# untitled.net
KiCad netlist of a schematic drawn in EAGLE
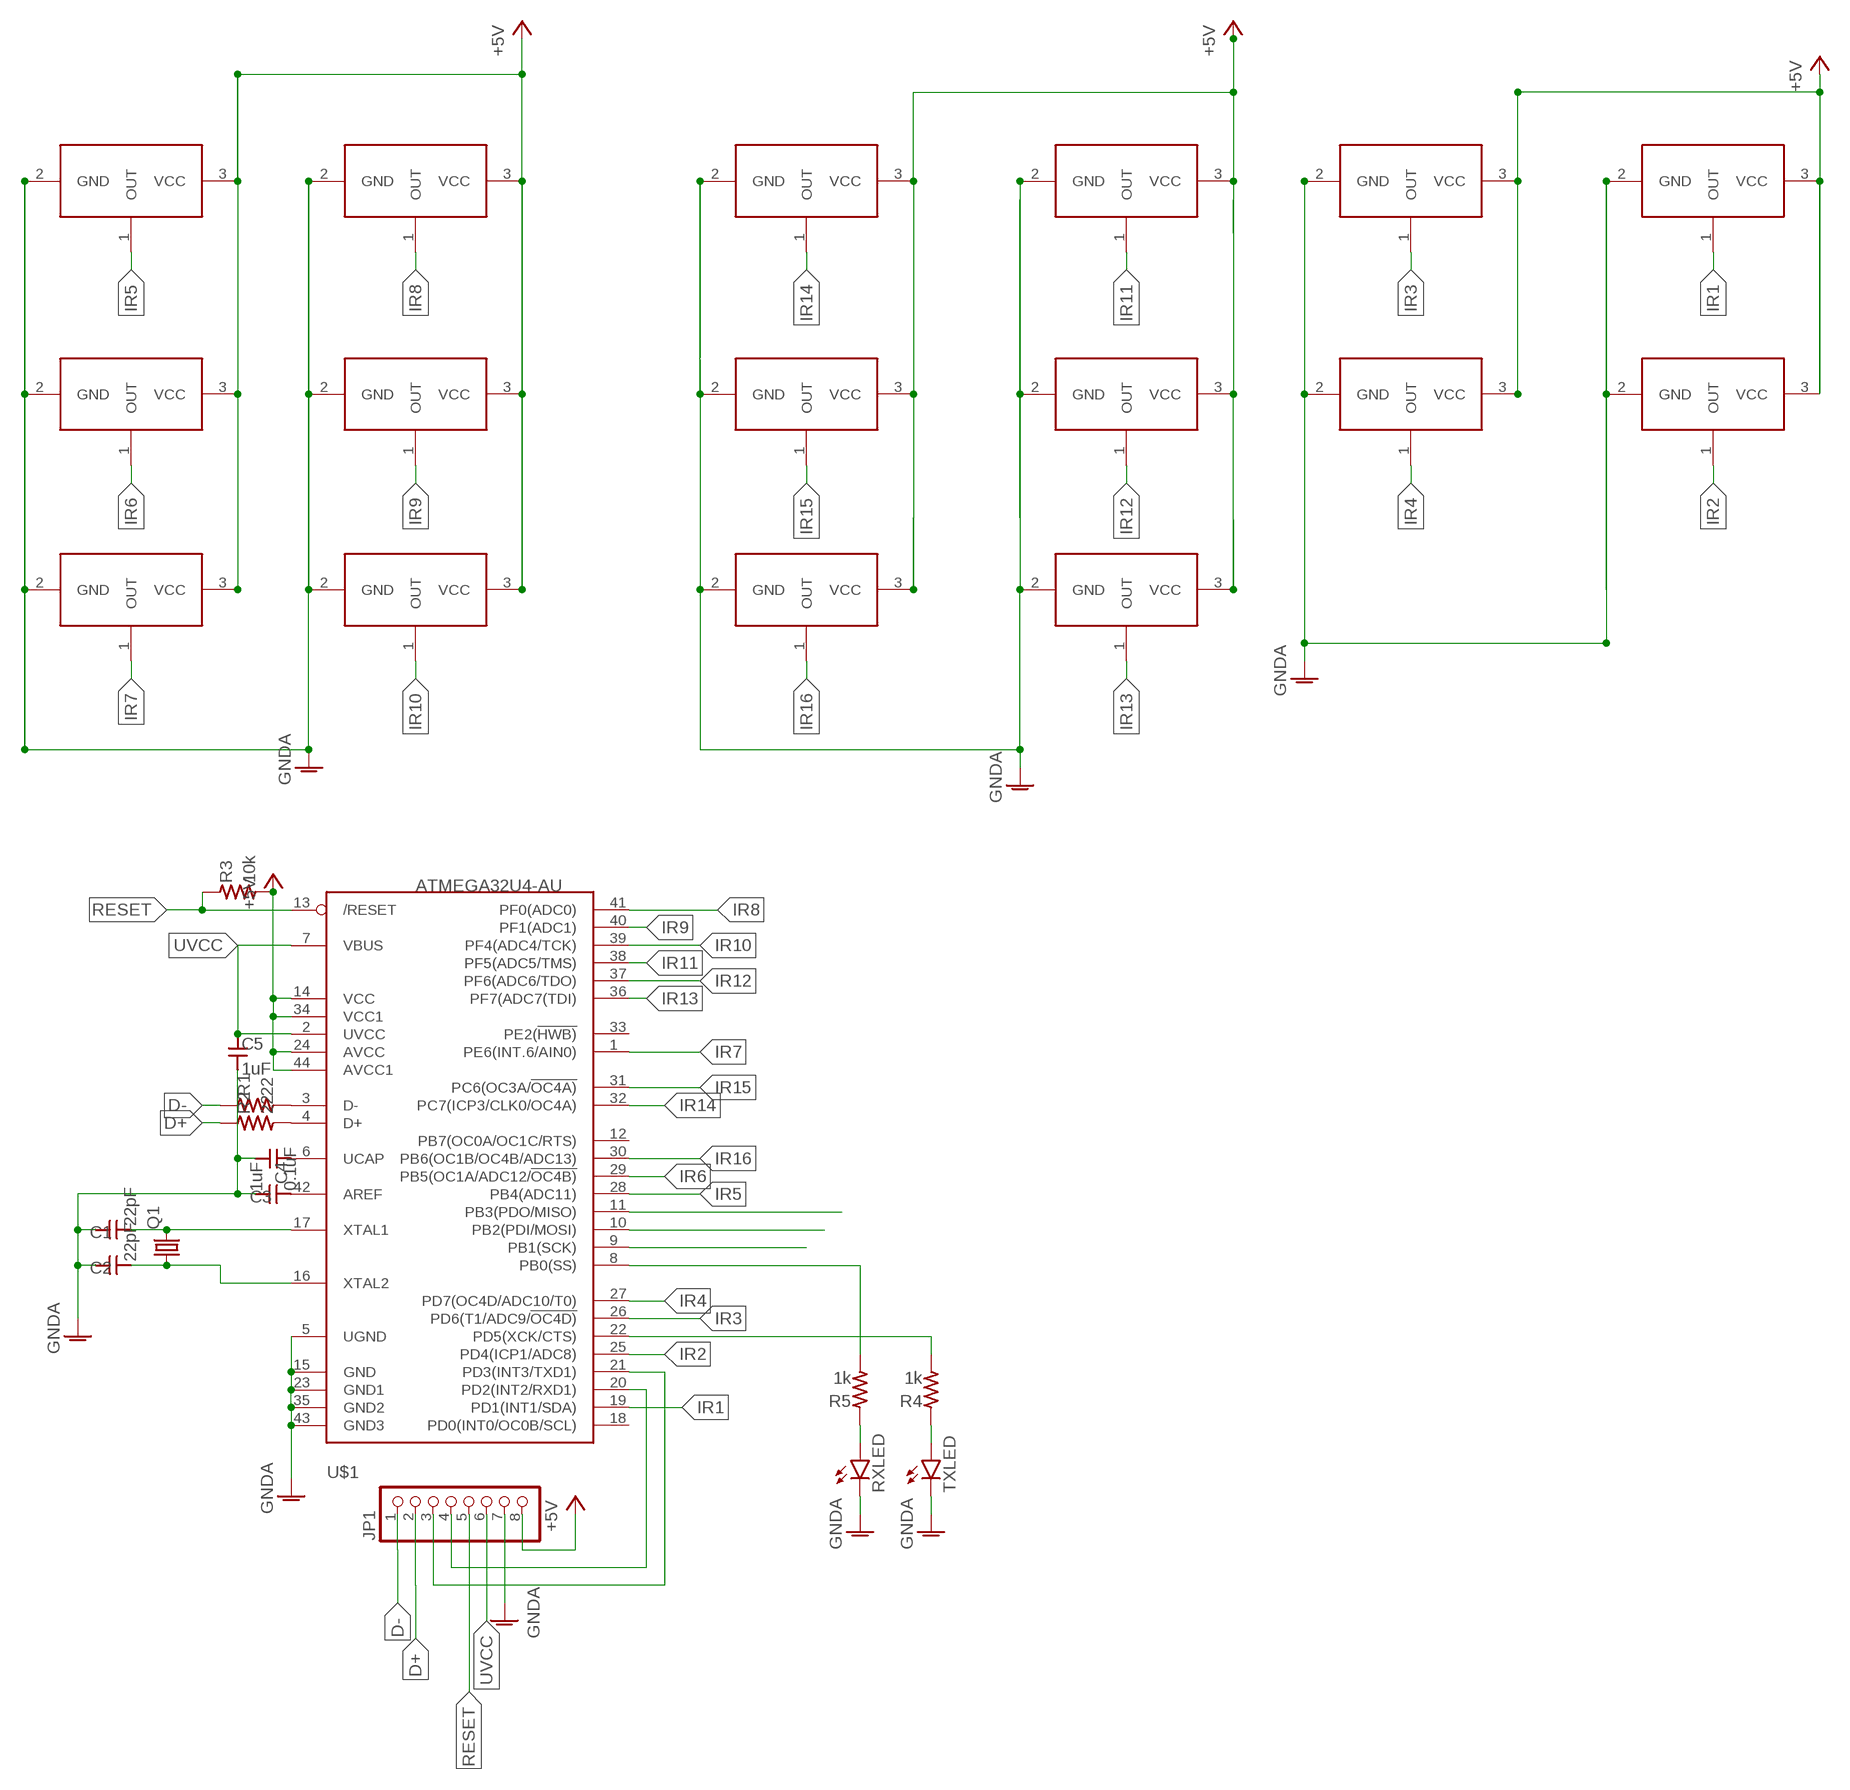
[diagram p0: schematic, sheet 1]

(export (version "E")
  (design (tool "Eeschema 10.0.6"))
  (components
    (comp (ref "C1")
      (value "22pF")
      (footprint "eagle-import:SMD1608")
      (libsource (lib "eagle-import") (part "CAPACITOR1608"))
    )
    (comp (ref "C2")
      (value "22pF")
      (footprint "eagle-import:SMD1608")
      (libsource (lib "eagle-import") (part "CAPACITOR1608"))
    )
    (comp (ref "C3")
      (value "0.1uF")
      (footprint "eagle-import:SMD1608")
      (libsource (lib "eagle-import") (part "CAPACITOR1608"))
    )
    (comp (ref "C4")
      (value "1uF")
      (footprint "eagle-import:SMD1608")
      (libsource (lib "eagle-import") (part "CAPACITOR1608"))
    )
    (comp (ref "C5")
      (value "1uF")
      (footprint "eagle-import:SMD1608")
      (libsource (lib "eagle-import") (part "CAPACITOR1608"))
    )
    (comp (ref "IR1")
      (value "IRM2121-A538")
      (footprint "eagle-import:IRM_V")
      (libsource (lib "eagle-import") (part "IRM2121-A538"))
    )
    (comp (ref "IR2")
      (value "IRM2121-A538")
      (footprint "eagle-import:IRM_V")
      (libsource (lib "eagle-import") (part "IRM2121-A538"))
    )
    (comp (ref "IR3")
      (value "IRM2121-A538")
      (footprint "eagle-import:IRM_V")
      (libsource (lib "eagle-import") (part "IRM2121-A538"))
    )
    (comp (ref "IR4")
      (value "IRM2121-A538")
      (footprint "eagle-import:IRM_V")
      (libsource (lib "eagle-import") (part "IRM2121-A538"))
    )
    (comp (ref "IR5")
      (value "IRM2121-A538")
      (footprint "eagle-import:IRM_V")
      (libsource (lib "eagle-import") (part "IRM2121-A538"))
    )
    (comp (ref "IR6")
      (value "IRM2121-A538")
      (footprint "eagle-import:IRM_V")
      (libsource (lib "eagle-import") (part "IRM2121-A538"))
    )
    (comp (ref "IR7")
      (value "IRM2121-A538")
      (footprint "eagle-import:IRM_V")
      (libsource (lib "eagle-import") (part "IRM2121-A538"))
    )
    (comp (ref "IR8")
      (value "IRM2121-A538")
      (footprint "eagle-import:IRM_V")
      (libsource (lib "eagle-import") (part "IRM2121-A538"))
    )
    (comp (ref "IR9")
      (value "IRM2121-A538")
      (footprint "eagle-import:IRM_V")
      (libsource (lib "eagle-import") (part "IRM2121-A538"))
    )
    (comp (ref "IR10")
      (value "IRM2121-A538")
      (footprint "eagle-import:IRM_V")
      (libsource (lib "eagle-import") (part "IRM2121-A538"))
    )
    (comp (ref "IR11")
      (value "IRM2121-A538")
      (footprint "eagle-import:IRM_V")
      (libsource (lib "eagle-import") (part "IRM2121-A538"))
    )
    (comp (ref "IR12")
      (value "IRM2121-A538")
      (footprint "eagle-import:IRM_V")
      (libsource (lib "eagle-import") (part "IRM2121-A538"))
    )
    (comp (ref "IR13")
      (value "IRM2121-A538")
      (footprint "eagle-import:IRM_V")
      (libsource (lib "eagle-import") (part "IRM2121-A538"))
    )
    (comp (ref "IR14")
      (value "IRM2121-A538")
      (footprint "eagle-import:IRM_V")
      (libsource (lib "eagle-import") (part "IRM2121-A538"))
    )
    (comp (ref "IR15")
      (value "IRM2121-A538")
      (footprint "eagle-import:IRM_V")
      (libsource (lib "eagle-import") (part "IRM2121-A538"))
    )
    (comp (ref "IR16")
      (value "IRM2121-A538")
      (footprint "eagle-import:IRM_V")
      (libsource (lib "eagle-import") (part "IRM2121-A538"))
    )
    (comp (ref "JP1")
      (value "PINHD-1X8BIG")
      (footprint "eagle-import:1X08-BIG")
      (libsource (lib "eagle-import") (part "PINHD-1X8BIG"))
    )
    (comp (ref "Q1")
      (value "CRYSTALHC49S")
      (footprint "eagle-import:HC49_S")
      (libsource (lib "eagle-import") (part "CRYSTALHC49S"))
    )
    (comp (ref "R1")
      (value "22")
      (footprint "eagle-import:SMD1608")
      (libsource (lib "eagle-import") (part "RESISTOR-US1608"))
    )
    (comp (ref "R2")
      (value "22")
      (footprint "eagle-import:SMD1608")
      (libsource (lib "eagle-import") (part "RESISTOR-US1608"))
    )
    (comp (ref "R3")
      (value "10k")
      (footprint "eagle-import:SMD1608")
      (libsource (lib "eagle-import") (part "RESISTOR-US1608"))
    )
    (comp (ref "R4")
      (value "1k")
      (footprint "eagle-import:SMD1608")
      (libsource (lib "eagle-import") (part "RESISTOR-US1608"))
    )
    (comp (ref "R5")
      (value "1k")
      (footprint "eagle-import:SMD1608")
      (libsource (lib "eagle-import") (part "RESISTOR-US1608"))
    )
    (comp (ref "RXLED")
      (value "LEDSML0603")
      (footprint "eagle-import:SML0603")
      (libsource (lib "eagle-import") (part "LEDSML0603"))
    )
    (comp (ref "TXLED")
      (value "LEDSML0603")
      (footprint "eagle-import:SML0603")
      (libsource (lib "eagle-import") (part "LEDSML0603"))
    )
    (comp (ref "U$1")
      (value "ATMEGA32U4-AU")
      (footprint "eagle-import:TQFP44")
      (libsource (lib "eagle-import") (part "ATMEGA32U4-AU"))
    )
  )
  (nets
    (net (code "1") (name "+5V") (class "Default")
      (node (ref "IR1") (pin "3") (pinfunction "VCC_3") (pintype "power_in"))
      (node (ref "IR10") (pin "3") (pinfunction "VCC_3") (pintype "power_in"))
      (node (ref "IR11") (pin "3") (pinfunction "VCC_3") (pintype "power_in"))
      (node (ref "IR12") (pin "3") (pinfunction "VCC_3") (pintype "power_in"))
      (node (ref "IR13") (pin "3") (pinfunction "VCC_3") (pintype "power_in"))
      (node (ref "IR14") (pin "3") (pinfunction "VCC_3") (pintype "power_in"))
      (node (ref "IR15") (pin "3") (pinfunction "VCC_3") (pintype "power_in"))
      (node (ref "IR16") (pin "3") (pinfunction "VCC_3") (pintype "power_in"))
      (node (ref "IR2") (pin "3") (pinfunction "VCC_3") (pintype "power_in"))
      (node (ref "IR3") (pin "3") (pinfunction "VCC_3") (pintype "power_in"))
      (node (ref "IR4") (pin "3") (pinfunction "VCC_3") (pintype "power_in"))
      (node (ref "IR5") (pin "3") (pinfunction "VCC_3") (pintype "power_in"))
      (node (ref "IR6") (pin "3") (pinfunction "VCC_3") (pintype "power_in"))
      (node (ref "IR7") (pin "3") (pinfunction "VCC_3") (pintype "power_in"))
      (node (ref "IR8") (pin "3") (pinfunction "VCC_3") (pintype "power_in"))
      (node (ref "IR9") (pin "3") (pinfunction "VCC_3") (pintype "power_in"))
      (node (ref "JP1") (pin "8") (pinfunction "8_8") (pintype "passive"))
      (node (ref "R3") (pin "2") (pinfunction "2_2") (pintype "passive"))
      (node (ref "U$1") (pin "14") (pinfunction "VCC_14") (pintype "bidirectional"))
      (node (ref "U$1") (pin "24") (pinfunction "AVCC_24") (pintype "bidirectional"))
      (node (ref "U$1") (pin "34") (pinfunction "VCC1_34") (pintype "bidirectional"))
      (node (ref "U$1") (pin "44") (pinfunction "AVCC1_44") (pintype "bidirectional"))
    )
    (net (code "2") (name "D+") (class "Default")
      (node (ref "JP1") (pin "2") (pinfunction "2_2") (pintype "passive"))
      (node (ref "R2") (pin "1") (pinfunction "1_1") (pintype "passive"))
    )
    (net (code "3") (name "D-") (class "Default")
      (node (ref "JP1") (pin "1") (pinfunction "1_1") (pintype "passive"))
      (node (ref "R1") (pin "1") (pinfunction "1_1") (pintype "passive"))
    )
    (net (code "4") (name "GNDA") (class "Default")
      (node (ref "C1") (pin "1") (pinfunction "1_1") (pintype "passive"))
      (node (ref "C2") (pin "1") (pinfunction "1_1") (pintype "passive"))
      (node (ref "C3") (pin "1") (pinfunction "1_1") (pintype "passive"))
      (node (ref "C4") (pin "2") (pinfunction "2_2") (pintype "passive"))
      (node (ref "C5") (pin "2") (pinfunction "2_2") (pintype "passive"))
      (node (ref "IR1") (pin "2") (pinfunction "GND_2") (pintype "power_in"))
      (node (ref "IR10") (pin "2") (pinfunction "GND_2") (pintype "power_in"))
      (node (ref "IR11") (pin "2") (pinfunction "GND_2") (pintype "power_in"))
      (node (ref "IR12") (pin "2") (pinfunction "GND_2") (pintype "power_in"))
      (node (ref "IR13") (pin "2") (pinfunction "GND_2") (pintype "power_in"))
      (node (ref "IR14") (pin "2") (pinfunction "GND_2") (pintype "power_in"))
      (node (ref "IR15") (pin "2") (pinfunction "GND_2") (pintype "power_in"))
      (node (ref "IR16") (pin "2") (pinfunction "GND_2") (pintype "power_in"))
      (node (ref "IR2") (pin "2") (pinfunction "GND_2") (pintype "power_in"))
      (node (ref "IR3") (pin "2") (pinfunction "GND_2") (pintype "power_in"))
      (node (ref "IR4") (pin "2") (pinfunction "GND_2") (pintype "power_in"))
      (node (ref "IR5") (pin "2") (pinfunction "GND_2") (pintype "power_in"))
      (node (ref "IR6") (pin "2") (pinfunction "GND_2") (pintype "power_in"))
      (node (ref "IR7") (pin "2") (pinfunction "GND_2") (pintype "power_in"))
      (node (ref "IR8") (pin "2") (pinfunction "GND_2") (pintype "power_in"))
      (node (ref "IR9") (pin "2") (pinfunction "GND_2") (pintype "power_in"))
      (node (ref "JP1") (pin "7") (pinfunction "7_7") (pintype "passive"))
      (node (ref "RXLED") (pin "C") (pinfunction "C_C") (pintype "passive"))
      (node (ref "TXLED") (pin "C") (pinfunction "C_C") (pintype "passive"))
      (node (ref "U$1") (pin "15") (pinfunction "GND_15") (pintype "bidirectional"))
      (node (ref "U$1") (pin "23") (pinfunction "GND1_23") (pintype "bidirectional"))
      (node (ref "U$1") (pin "35") (pinfunction "GND2_35") (pintype "bidirectional"))
      (node (ref "U$1") (pin "43") (pinfunction "GND3_43") (pintype "bidirectional"))
      (node (ref "U$1") (pin "5") (pinfunction "UGND_5") (pintype "bidirectional"))
    )
    (net (code "5") (name "IR1") (class "Default")
      (node (ref "IR1") (pin "1") (pinfunction "OUT_1") (pintype "bidirectional"))
      (node (ref "U$1") (pin "19") (pinfunction "PD1(INT1/SDA)_19") (pintype "bidirectional"))
    )
    (net (code "6") (name "IR2") (class "Default")
      (node (ref "IR2") (pin "1") (pinfunction "OUT_1") (pintype "bidirectional"))
      (node (ref "U$1") (pin "25") (pinfunction "PD4(ICP1/ADC8)_25") (pintype "bidirectional"))
    )
    (net (code "7") (name "IR3") (class "Default")
      (node (ref "IR3") (pin "1") (pinfunction "OUT_1") (pintype "bidirectional"))
      (node (ref "U$1") (pin "26") (pinfunction "PD6(T1/ADC9/~{OC4D})_26") (pintype "bidirectional"))
    )
    (net (code "8") (name "IR4") (class "Default")
      (node (ref "IR4") (pin "1") (pinfunction "OUT_1") (pintype "bidirectional"))
      (node (ref "U$1") (pin "27") (pinfunction "PD7(OC4D/ADC10/T0)_27") (pintype "bidirectional"))
    )
    (net (code "9") (name "IR5") (class "Default")
      (node (ref "IR5") (pin "1") (pinfunction "OUT_1") (pintype "bidirectional"))
      (node (ref "U$1") (pin "28") (pinfunction "PB4(ADC11)_28") (pintype "bidirectional"))
    )
    (net (code "10") (name "IR6") (class "Default")
      (node (ref "IR6") (pin "1") (pinfunction "OUT_1") (pintype "bidirectional"))
      (node (ref "U$1") (pin "29") (pinfunction "PB5(OC1A/ADC12/~{OC4B})_29") (pintype "bidirectional"))
    )
    (net (code "11") (name "IR7") (class "Default")
      (node (ref "IR7") (pin "1") (pinfunction "OUT_1") (pintype "bidirectional"))
      (node (ref "U$1") (pin "1") (pinfunction "PE6(INT.6/AIN0)_1") (pintype "bidirectional"))
    )
    (net (code "12") (name "IR8") (class "Default")
      (node (ref "IR8") (pin "1") (pinfunction "OUT_1") (pintype "bidirectional"))
      (node (ref "U$1") (pin "41") (pinfunction "PF0(ADC0)_41") (pintype "bidirectional"))
    )
    (net (code "13") (name "IR9") (class "Default")
      (node (ref "IR9") (pin "1") (pinfunction "OUT_1") (pintype "bidirectional"))
      (node (ref "U$1") (pin "40") (pinfunction "PF1(ADC1)_40") (pintype "bidirectional"))
    )
    (net (code "14") (name "IR10") (class "Default")
      (node (ref "IR10") (pin "1") (pinfunction "OUT_1") (pintype "bidirectional"))
      (node (ref "U$1") (pin "39") (pinfunction "PF4(ADC4/TCK)_39") (pintype "bidirectional"))
    )
    (net (code "15") (name "IR11") (class "Default")
      (node (ref "IR11") (pin "1") (pinfunction "OUT_1") (pintype "bidirectional"))
      (node (ref "U$1") (pin "38") (pinfunction "PF5(ADC5/TMS)_38") (pintype "bidirectional"))
    )
    (net (code "16") (name "IR12") (class "Default")
      (node (ref "IR12") (pin "1") (pinfunction "OUT_1") (pintype "bidirectional"))
      (node (ref "U$1") (pin "37") (pinfunction "PF6(ADC6/TDO)_37") (pintype "bidirectional"))
    )
    (net (code "17") (name "IR13") (class "Default")
      (node (ref "IR13") (pin "1") (pinfunction "OUT_1") (pintype "bidirectional"))
      (node (ref "U$1") (pin "36") (pinfunction "PF7(ADC7(TDI)_36") (pintype "bidirectional"))
    )
    (net (code "18") (name "IR14") (class "Default")
      (node (ref "IR14") (pin "1") (pinfunction "OUT_1") (pintype "bidirectional"))
      (node (ref "U$1") (pin "32") (pinfunction "PC7(ICP3/CLK0/OC4A)_32") (pintype "bidirectional"))
    )
    (net (code "19") (name "IR15") (class "Default")
      (node (ref "IR15") (pin "1") (pinfunction "OUT_1") (pintype "bidirectional"))
      (node (ref "U$1") (pin "31") (pinfunction "PC6(OC3A/~{OC4A})_31") (pintype "bidirectional"))
    )
    (net (code "20") (name "IR16") (class "Default")
      (node (ref "IR16") (pin "1") (pinfunction "OUT_1") (pintype "bidirectional"))
      (node (ref "U$1") (pin "30") (pinfunction "PB6(OC1B/OC4B/ADC13)_30") (pintype "bidirectional"))
    )
    (net (code "21") (name "Net-(R4-Pad1)") (class "Default")
      (node (ref "R4") (pin "1") (pinfunction "1_1") (pintype "passive"))
      (node (ref "TXLED") (pin "A") (pinfunction "A_A") (pintype "passive"))
    )
    (net (code "22") (name "Net-(R5-Pad1)") (class "Default")
      (node (ref "R5") (pin "1") (pinfunction "1_1") (pintype "passive"))
      (node (ref "RXLED") (pin "A") (pinfunction "A_A") (pintype "passive"))
    )
    (net (code "23") (name "Net-(U$1-AREF)") (class "Default")
      (node (ref "C3") (pin "2") (pinfunction "2_2") (pintype "passive"))
      (node (ref "U$1") (pin "42") (pinfunction "AREF_42") (pintype "bidirectional"))
    )
    (net (code "24") (name "Net-(U$1-D+)") (class "Default")
      (node (ref "R2") (pin "2") (pinfunction "2_2") (pintype "passive"))
      (node (ref "U$1") (pin "4") (pinfunction "D+_4") (pintype "bidirectional"))
    )
    (net (code "25") (name "Net-(U$1-D-)") (class "Default")
      (node (ref "R1") (pin "2") (pinfunction "2_2") (pintype "passive"))
      (node (ref "U$1") (pin "3") (pinfunction "D-_3") (pintype "bidirectional"))
    )
    (net (code "26") (name "Net-(U$1-PB0(SS))") (class "Default")
      (node (ref "R5") (pin "2") (pinfunction "2_2") (pintype "passive"))
      (node (ref "U$1") (pin "8") (pinfunction "PB0(SS)_8") (pintype "bidirectional"))
    )
    (net (code "27") (name "Net-(U$1-PD2(INT2{slash}RXD1))") (class "Default")
      (node (ref "JP1") (pin "4") (pinfunction "4_4") (pintype "passive"))
      (node (ref "U$1") (pin "20") (pinfunction "PD2(INT2/RXD1)_20") (pintype "bidirectional"))
    )
    (net (code "28") (name "Net-(U$1-PD3(INT3{slash}TXD1))") (class "Default")
      (node (ref "JP1") (pin "3") (pinfunction "3_3") (pintype "passive"))
      (node (ref "U$1") (pin "21") (pinfunction "PD3(INT3/TXD1)_21") (pintype "bidirectional"))
    )
    (net (code "29") (name "Net-(U$1-PD5(XCK{slash}CTS))") (class "Default")
      (node (ref "R4") (pin "2") (pinfunction "2_2") (pintype "passive"))
      (node (ref "U$1") (pin "22") (pinfunction "PD5(XCK/CTS)_22") (pintype "bidirectional"))
    )
    (net (code "30") (name "Net-(U$1-UCAP)") (class "Default")
      (node (ref "C4") (pin "1") (pinfunction "1_1") (pintype "passive"))
      (node (ref "U$1") (pin "6") (pinfunction "UCAP_6") (pintype "bidirectional"))
    )
    (net (code "31") (name "Net-(U$1-XTAL1)") (class "Default")
      (node (ref "C1") (pin "2") (pinfunction "2_2") (pintype "passive"))
      (node (ref "Q1") (pin "2") (pinfunction "2_2") (pintype "passive"))
      (node (ref "U$1") (pin "17") (pinfunction "XTAL1_17") (pintype "bidirectional"))
    )
    (net (code "32") (name "Net-(U$1-XTAL2)") (class "Default")
      (node (ref "C2") (pin "2") (pinfunction "2_2") (pintype "passive"))
      (node (ref "Q1") (pin "1") (pinfunction "1_1") (pintype "passive"))
      (node (ref "U$1") (pin "16") (pinfunction "XTAL2_16") (pintype "bidirectional"))
    )
    (net (code "33") (name "RESET") (class "Default")
      (node (ref "JP1") (pin "5") (pinfunction "5_5") (pintype "passive"))
      (node (ref "R3") (pin "1") (pinfunction "1_1") (pintype "passive"))
      (node (ref "U$1") (pin "13") (pinfunction "/RESET_13") (pintype "bidirectional"))
    )
    (net (code "34") (name "UVCC") (class "Default")
      (node (ref "C5") (pin "1") (pinfunction "1_1") (pintype "passive"))
      (node (ref "JP1") (pin "6") (pinfunction "6_6") (pintype "passive"))
      (node (ref "U$1") (pin "2") (pinfunction "UVCC_2") (pintype "bidirectional"))
      (node (ref "U$1") (pin "7") (pinfunction "VBUS_7") (pintype "bidirectional"))
    )
    (net (code "35") (name "unconnected-(U$1-PB1(SCK)-Pad9)") (class "Default")
      (node (ref "U$1") (pin "9") (pinfunction "PB1(SCK)_9") (pintype "bidirectional"))
    )
    (net (code "36") (name "unconnected-(U$1-PB2(PDI{slash}MOSI)-Pad10)") (class "Default")
      (node (ref "U$1") (pin "10") (pinfunction "PB2(PDI/MOSI)_10") (pintype "bidirectional"))
    )
    (net (code "37") (name "unconnected-(U$1-PB3(PDO{slash}MISO)-Pad11)") (class "Default")
      (node (ref "U$1") (pin "11") (pinfunction "PB3(PDO/MISO)_11") (pintype "bidirectional"))
    )
    (net (code "38") (name "unconnected-(U$1-PB7(OC0A{slash}OC1C{slash}RTS)-Pad12)") (class "Default")
      (node (ref "U$1") (pin "12") (pinfunction "PB7(OC0A/OC1C/RTS)_12") (pintype "bidirectional"))
    )
    (net (code "39") (name "unconnected-(U$1-PD0(INT0{slash}OC0B{slash}SCL)-Pad18)") (class "Default")
      (node (ref "U$1") (pin "18") (pinfunction "PD0(INT0/OC0B/SCL)_18") (pintype "bidirectional"))
    )
    (net (code "40") (name "unconnected-(U$1-PE2(~{HWB})-Pad33)") (class "Default")
      (node (ref "U$1") (pin "33") (pinfunction "PE2(~{HWB})_33") (pintype "bidirectional"))
    )
  )
)
